# RTU_LMG_gps_acond.net
KiCad netlist of a schematic drawn in Altium Designer
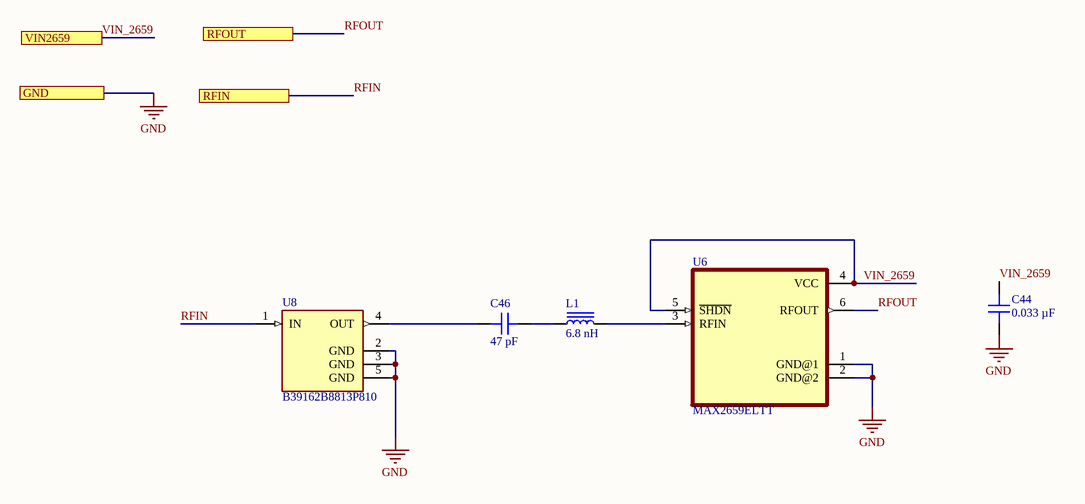
[diagram p0: RTU_LMG_gps_acond.SchDoc]

(export (version "E")
  (design (tool "Eeschema 10.0.6"))
  (components
    (comp (ref "C44")
      (value "0.033 µF")
      (footprint "CAP 0603_1608")
      (description "CAP CER 0603 33NF 16V X7R 5%")
      (fields
        (field (name "PART NUMBER") "C0603C333J4REC7411")
        (field (name "CAPACITANCE") "0.033 µF")
        (field (name "MANUFACTURER") "KEMET")
      )
      (libsource (lib "Celestial Altium Library - altium_library") (part "Capacitor"))
    )
    (comp (ref "C46")
      (value "47 pF")
      (footprint "CAP 0603_1608")
      (description "CAP CER 47PF 16V C0G/NP0 0603")
      (fields
        (field (name "PART NUMBER") "885012006021")
        (field (name "CAPACITANCE") "47 pF")
        (field (name "MANUFACTURER") "Würth Elektronik")
      )
      (libsource (lib "Celestial Altium Library - altium_library") (part "Capacitor"))
    )
    (comp (ref "L1")
      (value "6.8 nH")
      (footprint "INDC1005X55N")
      (description "FIXED IND 6.8NH 600MA 0.24OHM SM")
      (fields
        (field (name "PART NUMBER") "LQG15HH6N8J02D")
        (field (name "MANUFACTURER") "Murata Electronics")
      )
      (libsource (lib "Celestial Altium Library - altium_library") (part "Inductor"))
    )
    (comp (ref "U6")
      (value "MAX2659ELTT")
      (footprint "SON50P150X100X80-6N")
      (description "GPS/GNSS Low-Noise Amplifier")
      (fields (field (name "MF") "Analog Devices") (field (name "MP") "MAX2659ELT+T"))
      (libsource (lib "MAX2659ELTT") (part "MAX2659ELTT"))
    )
    (comp (ref "U8")
      (value "B39162B8813P810")
      (footprint "FIL_B39162B9417K610")
      (description "SAW Filter RF 1582.47MHz 1.9dB 50Ohm SMD 5 Pin SMT")
      (fields (field (name "MF") "RF 360"))
      (libsource (lib "B39162B8813P810") (part "B39162B8813P810"))
    )
  )
  (nets
    (net (code "1") (name "/RFIN") (class "Default")
      (node (ref "U8") (pin "1") (pinfunction "IN_1") (pintype "input"))
    )
    (net (code "2") (name "/RFOUT") (class "Default")
      (node (ref "U6") (pin "6") (pinfunction "RFOUT_6") (pintype "output"))
    )
    (net (code "3") (name "/VIN_2659") (class "Default")
      (node (ref "C44") (pin "2") (pinfunction "2_2") (pintype "passive"))
      (node (ref "U6") (pin "4") (pinfunction "VCC_4") (pintype "power_in"))
      (node (ref "U6") (pin "5") (pinfunction "~{SHDN}_5") (pintype "input"))
    )
    (net (code "4") (name "GND") (class "Default")
      (node (ref "C44") (pin "1") (pinfunction "1_1") (pintype "passive"))
      (node (ref "U6") (pin "1") (pinfunction "GND@1_1") (pintype "power_in"))
      (node (ref "U6") (pin "2") (pinfunction "GND@2_2") (pintype "power_in"))
      (node (ref "U8") (pin "2") (pinfunction "GND_2") (pintype "power_in"))
      (node (ref "U8") (pin "3") (pinfunction "GND_3") (pintype "power_in"))
      (node (ref "U8") (pin "5") (pinfunction "GND_5") (pintype "power_in"))
    )
    (net (code "5") (name "Net-(C46-Pad2)") (class "Default")
      (node (ref "C46") (pin "2") (pinfunction "2_2") (pintype "passive"))
      (node (ref "L1") (pin "1") (pinfunction "1_1") (pintype "passive"))
    )
    (net (code "6") (name "Net-(U6-RFIN)") (class "Default")
      (node (ref "L1") (pin "2") (pinfunction "2_2") (pintype "passive"))
      (node (ref "U6") (pin "3") (pinfunction "RFIN_3") (pintype "input"))
    )
    (net (code "7") (name "Net-(U8-OUT)") (class "Default")
      (node (ref "C46") (pin "1") (pinfunction "1_1") (pintype "passive"))
      (node (ref "U8") (pin "4") (pinfunction "OUT_4") (pintype "output"))
    )
  )
)
